# SDIO_SD_CARD.net
KiCad netlist of a schematic drawn in Altium Designer
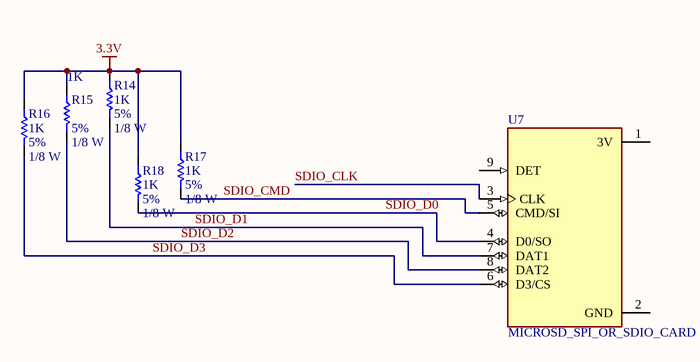
[diagram p0: SDIO_SD_CARD.SchDoc]

(export (version "E")
  (design (tool "Eeschema 10.0.6"))
  (components
    (comp (ref "R14")
      (value "1K")
      (footprint "RES 0805 (2012X06L)")
      (description "Resistor")
      (fields (field (name "TOLERANCE") "5%") (field (name "POWER") "1/8 W"))
      (libsource (lib "My Library") (part "Resistor"))
    )
    (comp (ref "R15")
      (value "1K")
      (footprint "RES 0805 (2012X06L)")
      (description "Resistor")
      (fields (field (name "TOLERANCE") "5%") (field (name "POWER") "1/8 W"))
      (libsource (lib "My Library") (part "Resistor"))
    )
    (comp (ref "R16")
      (value "1K")
      (footprint "RES 0805 (2012X06L)")
      (description "Resistor")
      (fields (field (name "TOLERANCE") "5%") (field (name "POWER") "1/8 W"))
      (libsource (lib "My Library") (part "Resistor"))
    )
    (comp (ref "R17")
      (value "1K")
      (footprint "RES 0805 (2012X06L)")
      (description "Resistor")
      (fields (field (name "TOLERANCE") "5%") (field (name "POWER") "1/8 W"))
      (libsource (lib "My Library") (part "Resistor"))
    )
    (comp (ref "R18")
      (value "1K")
      (footprint "RES 0805 (2012X06L)")
      (description "Resistor")
      (fields (field (name "TOLERANCE") "5%") (field (name "POWER") "1/8 W"))
      (libsource (lib "My Library") (part "Resistor"))
    )
    (comp (ref "U7")
      (value "MICROSD_SPI_OR_SDIO_CARD")
      (footprint "MODULE_MICROSD_SPI_OR_SDIO_CARD")
      (description "Memory Card Connectors Raspberry pi microSD card adapter")
      (fields (field (name "MF") "Adafruit Industries") (field (name "MP") "MicroSD SPI or SDIO Card"))
      (libsource (lib "MICROSD_SPI_OR_SDIO_CARD") (part "MICROSD_SPI_OR_SDIO_CARD"))
    )
  )
  (nets
    (net (code "1") (name "/SDIO_CLK") (class "Default")
      (node (ref "U7") (pin "3") (pinfunction "CLK_3") (pintype "input"))
    )
    (net (code "2") (name "/SDIO_CMD") (class "Default")
      (node (ref "R17") (pin "2") (pinfunction "2_2") (pintype "passive"))
      (node (ref "U7") (pin "5") (pinfunction "CMD/SI_5") (pintype "bidirectional"))
    )
    (net (code "3") (name "/SDIO_D0") (class "Default")
      (node (ref "R18") (pin "2") (pinfunction "2_2") (pintype "passive"))
      (node (ref "U7") (pin "4") (pinfunction "D0/SO_4") (pintype "bidirectional"))
    )
    (net (code "4") (name "/SDIO_D1") (class "Default")
      (node (ref "R14") (pin "2") (pinfunction "2_2") (pintype "passive"))
      (node (ref "U7") (pin "7") (pinfunction "DAT1_7") (pintype "bidirectional"))
    )
    (net (code "5") (name "/SDIO_D2") (class "Default")
      (node (ref "R15") (pin "2") (pinfunction "2_2") (pintype "passive"))
      (node (ref "U7") (pin "8") (pinfunction "DAT2_8") (pintype "bidirectional"))
    )
    (net (code "6") (name "/SDIO_D3") (class "Default")
      (node (ref "R16") (pin "2") (pinfunction "2_2") (pintype "passive"))
      (node (ref "U7") (pin "6") (pinfunction "D3/CS_6") (pintype "bidirectional"))
    )
    (net (code "7") (name "3.3V") (class "Default")
      (node (ref "R14") (pin "1") (pinfunction "1_1") (pintype "passive"))
      (node (ref "R15") (pin "1") (pinfunction "1_1") (pintype "passive"))
      (node (ref "R16") (pin "1") (pinfunction "1_1") (pintype "passive"))
      (node (ref "R17") (pin "1") (pinfunction "1_1") (pintype "passive"))
      (node (ref "R18") (pin "1") (pinfunction "1_1") (pintype "passive"))
    )
    (net (code "8") (name "unconnected-(U7-3V-Pad1)") (class "Default")
      (node (ref "U7") (pin "1") (pinfunction "3V_1") (pintype "power_in"))
    )
    (net (code "9") (name "unconnected-(U7-DET-Pad9)") (class "Default")
      (node (ref "U7") (pin "9") (pinfunction "DET_9") (pintype "input"))
    )
    (net (code "10") (name "unconnected-(U7-GND-Pad2)") (class "Default")
      (node (ref "U7") (pin "2") (pinfunction "GND_2") (pintype "power_in"))
    )
  )
)
